# main.net
KiCad netlist of a schematic drawn in EAGLE
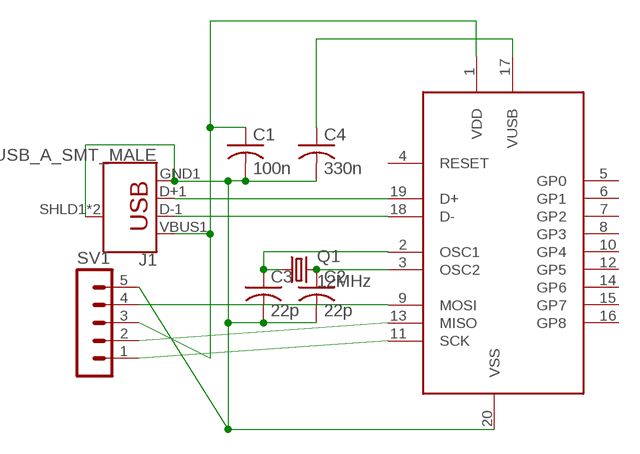
[diagram p0: schematic, sheet 1]

(export (version "E")
  (design (tool "Eeschema 10.0.6"))
  (components
    (comp (ref "C1")
      (value "100n")
      (footprint "eagle-import:C0805")
      (libsource (lib "eagle-import") (part "C-USC0805"))
    )
    (comp (ref "C2")
      (value "22p")
      (footprint "eagle-import:C0603")
      (libsource (lib "eagle-import") (part "C-USC0603"))
    )
    (comp (ref "C3")
      (value "22p")
      (footprint "eagle-import:C0603")
      (libsource (lib "eagle-import") (part "C-USC0603"))
    )
    (comp (ref "C4")
      (value "330n")
      (footprint "eagle-import:C0603")
      (libsource (lib "eagle-import") (part "C-USC0603"))
    )
    (comp (ref "J1")
      (value "USB_A_SMT_MALE")
      (footprint "eagle-import:USB-A-SMT-MALE")
      (libsource (lib "eagle-import") (part "USB_A_SMT_MALE"))
    )
    (comp (ref "Q1")
      (value "12MHz")
      (footprint "eagle-import:HC49U-V")
      (libsource (lib "eagle-import") (part "CRYSTALHC49U-V"))
    )
    (comp (ref "SV1")
      (value "MA05-1")
      (footprint "eagle-import:MA05-1")
      (libsource (lib "eagle-import") (part "MA05-1"))
    )
    (comp (ref "U$1")
      (value "MCP2210")
      (footprint "eagle-import:SOIC20_GENERIC")
      (libsource (lib "eagle-import") (part "MCP2210"))
    )
  )
  (nets
    (net (code "1") (name "Net-(J1-D+)") (class "Default")
      (node (ref "J1") (pin "D+1") (pinfunction "D+_D+1") (pintype "bidirectional"))
      (node (ref "U$1") (pin "19") (pinfunction "D+_19") (pintype "bidirectional"))
    )
    (net (code "2") (name "Net-(J1-D-)") (class "Default")
      (node (ref "J1") (pin "D-1") (pinfunction "D-_D-1") (pintype "bidirectional"))
      (node (ref "U$1") (pin "18") (pinfunction "D-_18") (pintype "bidirectional"))
    )
    (net (code "3") (name "Net-(J1-GND)") (class "Default")
      (node (ref "C1") (pin "2") (pinfunction "2_2") (pintype "passive"))
      (node (ref "C2") (pin "2") (pinfunction "2_2") (pintype "passive"))
      (node (ref "C3") (pin "2") (pinfunction "2_2") (pintype "passive"))
      (node (ref "C4") (pin "2") (pinfunction "2_2") (pintype "passive"))
      (node (ref "J1") (pin "GND1") (pinfunction "GND_GND1") (pintype "power_in"))
      (node (ref "J1") (pin "SHLD1") (pinfunction "SHIELD_SHLD1") (pintype "bidirectional"))
      (node (ref "J1") (pin "SHLD2") (pinfunction "SHIELD_SHLD2") (pintype "bidirectional"))
      (node (ref "SV1") (pin "5") (pinfunction "5_5") (pintype "passive"))
      (node (ref "U$1") (pin "20") (pinfunction "VSS_20") (pintype "bidirectional"))
    )
    (net (code "4") (name "Net-(J1-VBUS)") (class "Default")
      (node (ref "C1") (pin "1") (pinfunction "1_1") (pintype "passive"))
      (node (ref "J1") (pin "VBUS1") (pinfunction "VBUS_VBUS1") (pintype "power_in"))
      (node (ref "SV1") (pin "3") (pinfunction "3_3") (pintype "passive"))
      (node (ref "U$1") (pin "1") (pinfunction "VDD_1") (pintype "bidirectional"))
    )
    (net (code "5") (name "Net-(U$1-MISO)") (class "Default")
      (node (ref "SV1") (pin "2") (pinfunction "2_2") (pintype "passive"))
      (node (ref "U$1") (pin "13") (pinfunction "MISO_13") (pintype "bidirectional"))
    )
    (net (code "6") (name "Net-(U$1-MOSI)") (class "Default")
      (node (ref "SV1") (pin "4") (pinfunction "4_4") (pintype "passive"))
      (node (ref "U$1") (pin "9") (pinfunction "MOSI_9") (pintype "bidirectional"))
    )
    (net (code "7") (name "Net-(U$1-OSC1)") (class "Default")
      (node (ref "C3") (pin "1") (pinfunction "1_1") (pintype "passive"))
      (node (ref "Q1") (pin "1") (pinfunction "1_1") (pintype "passive"))
      (node (ref "U$1") (pin "2") (pinfunction "OSC1_2") (pintype "bidirectional"))
    )
    (net (code "8") (name "Net-(U$1-OSC2)") (class "Default")
      (node (ref "C2") (pin "1") (pinfunction "1_1") (pintype "passive"))
      (node (ref "Q1") (pin "2") (pinfunction "2_2") (pintype "passive"))
      (node (ref "U$1") (pin "3") (pinfunction "OSC2_3") (pintype "bidirectional"))
    )
    (net (code "9") (name "Net-(U$1-SCK)") (class "Default")
      (node (ref "SV1") (pin "1") (pinfunction "1_1") (pintype "passive"))
      (node (ref "U$1") (pin "11") (pinfunction "SCK_11") (pintype "bidirectional"))
    )
    (net (code "10") (name "Net-(U$1-VUSB)") (class "Default")
      (node (ref "C4") (pin "1") (pinfunction "1_1") (pintype "passive"))
      (node (ref "U$1") (pin "17") (pinfunction "VUSB_17") (pintype "bidirectional"))
    )
    (net (code "11") (name "unconnected-(U$1-GP0-Pad5)") (class "Default")
      (node (ref "U$1") (pin "5") (pinfunction "GP0_5") (pintype "bidirectional"))
    )
    (net (code "12") (name "unconnected-(U$1-GP1-Pad6)") (class "Default")
      (node (ref "U$1") (pin "6") (pinfunction "GP1_6") (pintype "bidirectional"))
    )
    (net (code "13") (name "unconnected-(U$1-GP2-Pad7)") (class "Default")
      (node (ref "U$1") (pin "7") (pinfunction "GP2_7") (pintype "bidirectional"))
    )
    (net (code "14") (name "unconnected-(U$1-GP3-Pad8)") (class "Default")
      (node (ref "U$1") (pin "8") (pinfunction "GP3_8") (pintype "bidirectional"))
    )
    (net (code "15") (name "unconnected-(U$1-GP4-Pad10)") (class "Default")
      (node (ref "U$1") (pin "10") (pinfunction "GP4_10") (pintype "bidirectional"))
    )
    (net (code "16") (name "unconnected-(U$1-GP5-Pad12)") (class "Default")
      (node (ref "U$1") (pin "12") (pinfunction "GP5_12") (pintype "bidirectional"))
    )
    (net (code "17") (name "unconnected-(U$1-GP6-Pad14)") (class "Default")
      (node (ref "U$1") (pin "14") (pinfunction "GP6_14") (pintype "bidirectional"))
    )
    (net (code "18") (name "unconnected-(U$1-GP7-Pad15)") (class "Default")
      (node (ref "U$1") (pin "15") (pinfunction "GP7_15") (pintype "bidirectional"))
    )
    (net (code "19") (name "unconnected-(U$1-GP8-Pad16)") (class "Default")
      (node (ref "U$1") (pin "16") (pinfunction "GP8_16") (pintype "bidirectional"))
    )
    (net (code "20") (name "unconnected-(U$1-RESET-Pad4)") (class "Default")
      (node (ref "U$1") (pin "4") (pinfunction "RESET_4") (pintype "bidirectional"))
    )
  )
)
